# P6_LED_SHIELD.net
KiCad netlist of a schematic drawn in EAGLE
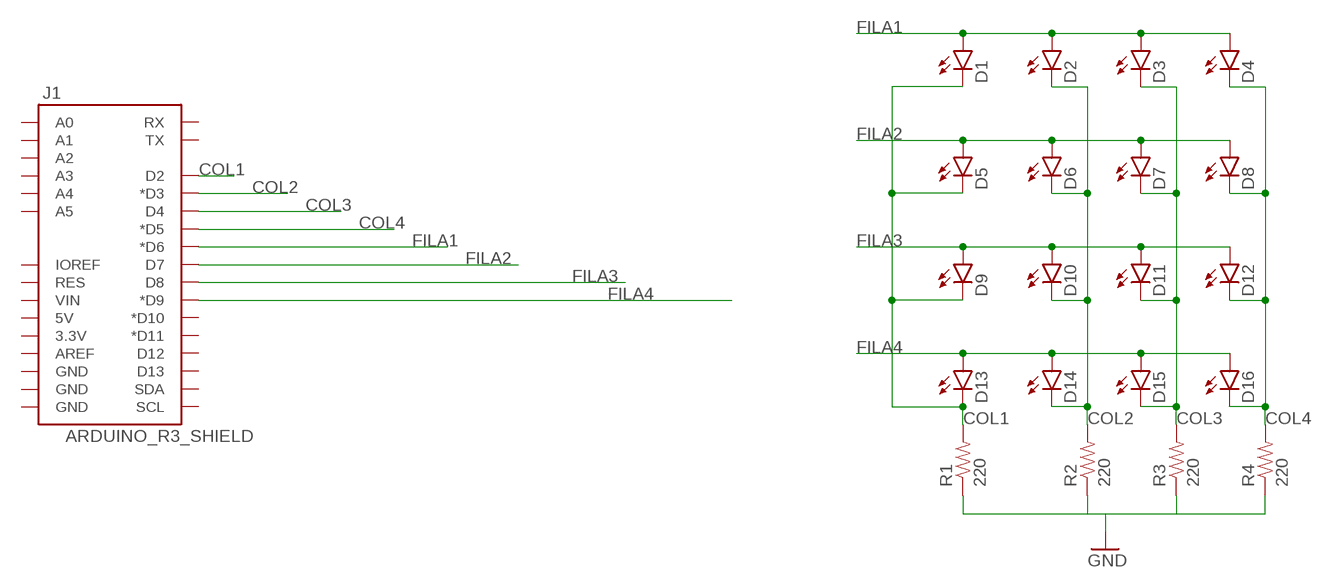
[diagram p0: schematic, sheet 1]

(export (version "E")
  (design (tool "Eeschema 10.0.6"))
  (components
    (comp (ref "D1")
      (value "LED5MM")
      (footprint "eagle-import:LED5MM")
      (libsource (lib "eagle-import") (part "LED5MM"))
    )
    (comp (ref "D2")
      (value "LED5MM")
      (footprint "eagle-import:LED5MM")
      (libsource (lib "eagle-import") (part "LED5MM"))
    )
    (comp (ref "D3")
      (value "LED5MM")
      (footprint "eagle-import:LED5MM")
      (libsource (lib "eagle-import") (part "LED5MM"))
    )
    (comp (ref "D4")
      (value "LED5MM")
      (footprint "eagle-import:LED5MM")
      (libsource (lib "eagle-import") (part "LED5MM"))
    )
    (comp (ref "D5")
      (value "LED5MM")
      (footprint "eagle-import:LED5MM")
      (libsource (lib "eagle-import") (part "LED5MM"))
    )
    (comp (ref "D6")
      (value "LED5MM")
      (footprint "eagle-import:LED5MM")
      (libsource (lib "eagle-import") (part "LED5MM"))
    )
    (comp (ref "D7")
      (value "LED5MM")
      (footprint "eagle-import:LED5MM")
      (libsource (lib "eagle-import") (part "LED5MM"))
    )
    (comp (ref "D8")
      (value "LED5MM")
      (footprint "eagle-import:LED5MM")
      (libsource (lib "eagle-import") (part "LED5MM"))
    )
    (comp (ref "D9")
      (value "LED5MM")
      (footprint "eagle-import:LED5MM")
      (libsource (lib "eagle-import") (part "LED5MM"))
    )
    (comp (ref "D10")
      (value "LED5MM")
      (footprint "eagle-import:LED5MM")
      (libsource (lib "eagle-import") (part "LED5MM"))
    )
    (comp (ref "D11")
      (value "LED5MM")
      (footprint "eagle-import:LED5MM")
      (libsource (lib "eagle-import") (part "LED5MM"))
    )
    (comp (ref "D12")
      (value "LED5MM")
      (footprint "eagle-import:LED5MM")
      (libsource (lib "eagle-import") (part "LED5MM"))
    )
    (comp (ref "D13")
      (value "LED5MM")
      (footprint "eagle-import:LED5MM")
      (libsource (lib "eagle-import") (part "LED5MM"))
    )
    (comp (ref "D14")
      (value "LED5MM")
      (footprint "eagle-import:LED5MM")
      (libsource (lib "eagle-import") (part "LED5MM"))
    )
    (comp (ref "D15")
      (value "LED5MM")
      (footprint "eagle-import:LED5MM")
      (libsource (lib "eagle-import") (part "LED5MM"))
    )
    (comp (ref "D16")
      (value "LED5MM")
      (footprint "eagle-import:LED5MM")
      (libsource (lib "eagle-import") (part "LED5MM"))
    )
    (comp (ref "J1")
      (value "ARDUINO_R3_SHIELD")
      (footprint "eagle-import:UNO_R3_SHIELD")
      (libsource (lib "eagle-import") (part "ARDUINO_R3_SHIELD"))
    )
    (comp (ref "R1")
      (value "220")
      (footprint "eagle-import:AXIAL-0.4")
      (libsource (lib "eagle-import") (part "RESISTORPTH-1/4W"))
    )
    (comp (ref "R2")
      (value "220")
      (footprint "eagle-import:AXIAL-0.4")
      (libsource (lib "eagle-import") (part "RESISTORPTH-1/4W"))
    )
    (comp (ref "R3")
      (value "220")
      (footprint "eagle-import:AXIAL-0.4")
      (libsource (lib "eagle-import") (part "RESISTORPTH-1/4W"))
    )
    (comp (ref "R4")
      (value "220")
      (footprint "eagle-import:AXIAL-0.4")
      (libsource (lib "eagle-import") (part "RESISTORPTH-1/4W"))
    )
  )
  (nets
    (net (code "1") (name "/COL1") (class "Default")
      (node (ref "D1") (pin "K") (pinfunction "C_K") (pintype "passive"))
      (node (ref "D13") (pin "K") (pinfunction "C_K") (pintype "passive"))
      (node (ref "D5") (pin "K") (pinfunction "C_K") (pintype "passive"))
      (node (ref "D9") (pin "K") (pinfunction "C_K") (pintype "passive"))
      (node (ref "J1") (pin "D2") (pinfunction "D2_D2") (pintype "bidirectional"))
      (node (ref "R1") (pin "P$2") (pinfunction "2_P$2") (pintype "passive"))
    )
    (net (code "2") (name "/COL2") (class "Default")
      (node (ref "D10") (pin "K") (pinfunction "C_K") (pintype "passive"))
      (node (ref "D14") (pin "K") (pinfunction "C_K") (pintype "passive"))
      (node (ref "D2") (pin "K") (pinfunction "C_K") (pintype "passive"))
      (node (ref "D6") (pin "K") (pinfunction "C_K") (pintype "passive"))
      (node (ref "J1") (pin "D3") (pinfunction "*D3_D3") (pintype "bidirectional"))
      (node (ref "R2") (pin "P$2") (pinfunction "2_P$2") (pintype "passive"))
    )
    (net (code "3") (name "/COL3") (class "Default")
      (node (ref "D11") (pin "K") (pinfunction "C_K") (pintype "passive"))
      (node (ref "D15") (pin "K") (pinfunction "C_K") (pintype "passive"))
      (node (ref "D3") (pin "K") (pinfunction "C_K") (pintype "passive"))
      (node (ref "D7") (pin "K") (pinfunction "C_K") (pintype "passive"))
      (node (ref "J1") (pin "D4") (pinfunction "D4_D4") (pintype "bidirectional"))
      (node (ref "R3") (pin "P$2") (pinfunction "2_P$2") (pintype "passive"))
    )
    (net (code "4") (name "/COL4") (class "Default")
      (node (ref "D12") (pin "K") (pinfunction "C_K") (pintype "passive"))
      (node (ref "D16") (pin "K") (pinfunction "C_K") (pintype "passive"))
      (node (ref "D4") (pin "K") (pinfunction "C_K") (pintype "passive"))
      (node (ref "D8") (pin "K") (pinfunction "C_K") (pintype "passive"))
      (node (ref "J1") (pin "D5") (pinfunction "*D5_D5") (pintype "bidirectional"))
      (node (ref "R4") (pin "P$2") (pinfunction "2_P$2") (pintype "passive"))
    )
    (net (code "5") (name "/FILA1") (class "Default")
      (node (ref "D1") (pin "A") (pinfunction "A_A") (pintype "passive"))
      (node (ref "D2") (pin "A") (pinfunction "A_A") (pintype "passive"))
      (node (ref "D3") (pin "A") (pinfunction "A_A") (pintype "passive"))
      (node (ref "D4") (pin "A") (pinfunction "A_A") (pintype "passive"))
      (node (ref "J1") (pin "D6") (pinfunction "*D6_D6") (pintype "bidirectional"))
    )
    (net (code "6") (name "/FILA2") (class "Default")
      (node (ref "D5") (pin "A") (pinfunction "A_A") (pintype "passive"))
      (node (ref "D6") (pin "A") (pinfunction "A_A") (pintype "passive"))
      (node (ref "D7") (pin "A") (pinfunction "A_A") (pintype "passive"))
      (node (ref "D8") (pin "A") (pinfunction "A_A") (pintype "passive"))
      (node (ref "J1") (pin "D7") (pinfunction "D7_D7") (pintype "bidirectional"))
    )
    (net (code "7") (name "/FILA3") (class "Default")
      (node (ref "D10") (pin "A") (pinfunction "A_A") (pintype "passive"))
      (node (ref "D11") (pin "A") (pinfunction "A_A") (pintype "passive"))
      (node (ref "D12") (pin "A") (pinfunction "A_A") (pintype "passive"))
      (node (ref "D9") (pin "A") (pinfunction "A_A") (pintype "passive"))
      (node (ref "J1") (pin "D8") (pinfunction "D8_D8") (pintype "bidirectional"))
    )
    (net (code "8") (name "/FILA4") (class "Default")
      (node (ref "D13") (pin "A") (pinfunction "A_A") (pintype "passive"))
      (node (ref "D14") (pin "A") (pinfunction "A_A") (pintype "passive"))
      (node (ref "D15") (pin "A") (pinfunction "A_A") (pintype "passive"))
      (node (ref "D16") (pin "A") (pinfunction "A_A") (pintype "passive"))
      (node (ref "J1") (pin "D9") (pinfunction "*D9_D9") (pintype "bidirectional"))
    )
    (net (code "9") (name "GND") (class "Default")
      (node (ref "R1") (pin "P$1") (pinfunction "1_P$1") (pintype "passive"))
      (node (ref "R2") (pin "P$1") (pinfunction "1_P$1") (pintype "passive"))
      (node (ref "R3") (pin "P$1") (pinfunction "1_P$1") (pintype "passive"))
      (node (ref "R4") (pin "P$1") (pinfunction "1_P$1") (pintype "passive"))
    )
    (net (code "10") (name "unconnected-(J1-*D10-PadD10)") (class "Default")
      (node (ref "J1") (pin "D10") (pinfunction "*D10_D10") (pintype "bidirectional"))
    )
    (net (code "11") (name "unconnected-(J1-*D11-PadD11)") (class "Default")
      (node (ref "J1") (pin "D11") (pinfunction "*D11_D11") (pintype "bidirectional"))
    )
    (net (code "12") (name "unconnected-(J1-GND-PadGND@0)") (class "Default")
      (node (ref "J1") (pin "GND@0") (pinfunction "GND_GND@0") (pintype "bidirectional"))
    )
    (net (code "13") (name "unconnected-(J1-GND-PadGND@1)") (class "Default")
      (node (ref "J1") (pin "GND@1") (pinfunction "GND_GND@1") (pintype "bidirectional"))
    )
    (net (code "14") (name "unconnected-(J1-GND-PadGND@2)") (class "Default")
      (node (ref "J1") (pin "GND@2") (pinfunction "GND_GND@2") (pintype "bidirectional"))
    )
    (net (code "15") (name "unconnected-(J1-Pad3.3V)") (class "Default")
      (node (ref "J1") (pin "3.3V") (pinfunction "3.3V_3.3V") (pintype "bidirectional"))
    )
    (net (code "16") (name "unconnected-(J1-Pad5V)") (class "Default")
      (node (ref "J1") (pin "5V") (pinfunction "5V_5V") (pintype "bidirectional"))
    )
    (net (code "17") (name "unconnected-(J1-PadA0)") (class "Default")
      (node (ref "J1") (pin "A0") (pinfunction "A0_A0") (pintype "bidirectional"))
    )
    (net (code "18") (name "unconnected-(J1-PadA1)") (class "Default")
      (node (ref "J1") (pin "A1") (pinfunction "A1_A1") (pintype "bidirectional"))
    )
    (net (code "19") (name "unconnected-(J1-PadA2)") (class "Default")
      (node (ref "J1") (pin "A2") (pinfunction "A2_A2") (pintype "bidirectional"))
    )
    (net (code "20") (name "unconnected-(J1-PadA3)") (class "Default")
      (node (ref "J1") (pin "A3") (pinfunction "A3_A3") (pintype "bidirectional"))
    )
    (net (code "21") (name "unconnected-(J1-PadA4)") (class "Default")
      (node (ref "J1") (pin "A4") (pinfunction "A4_A4") (pintype "bidirectional"))
    )
    (net (code "22") (name "unconnected-(J1-PadA5)") (class "Default")
      (node (ref "J1") (pin "A5") (pinfunction "A5_A5") (pintype "bidirectional"))
    )
    (net (code "23") (name "unconnected-(J1-PadAREF)") (class "Default")
      (node (ref "J1") (pin "AREF") (pinfunction "AREF_AREF") (pintype "bidirectional"))
    )
    (net (code "24") (name "unconnected-(J1-PadD12)") (class "Default")
      (node (ref "J1") (pin "D12") (pinfunction "D12_D12") (pintype "bidirectional"))
    )
    (net (code "25") (name "unconnected-(J1-PadD13)") (class "Default")
      (node (ref "J1") (pin "D13") (pinfunction "D13_D13") (pintype "bidirectional"))
    )
    (net (code "26") (name "unconnected-(J1-PadIOREF)") (class "Default")
      (node (ref "J1") (pin "IOREF") (pinfunction "IOREF_IOREF") (pintype "bidirectional"))
    )
    (net (code "27") (name "unconnected-(J1-PadRES)") (class "Default")
      (node (ref "J1") (pin "RES") (pinfunction "RES_RES") (pintype "bidirectional"))
    )
    (net (code "28") (name "unconnected-(J1-PadRX)") (class "Default")
      (node (ref "J1") (pin "RX") (pinfunction "RX_RX") (pintype "bidirectional"))
    )
    (net (code "29") (name "unconnected-(J1-PadSCL)") (class "Default")
      (node (ref "J1") (pin "SCL") (pinfunction "SCL_SCL") (pintype "bidirectional"))
    )
    (net (code "30") (name "unconnected-(J1-PadSDA)") (class "Default")
      (node (ref "J1") (pin "SDA") (pinfunction "SDA_SDA") (pintype "bidirectional"))
    )
    (net (code "31") (name "unconnected-(J1-PadTX)") (class "Default")
      (node (ref "J1") (pin "TX") (pinfunction "TX_TX") (pintype "bidirectional"))
    )
    (net (code "32") (name "unconnected-(J1-PadVIN)") (class "Default")
      (node (ref "J1") (pin "VIN") (pinfunction "VIN_VIN") (pintype "bidirectional"))
    )
  )
)
